# photo-trigger.net
KiCad netlist of a schematic drawn in EAGLE
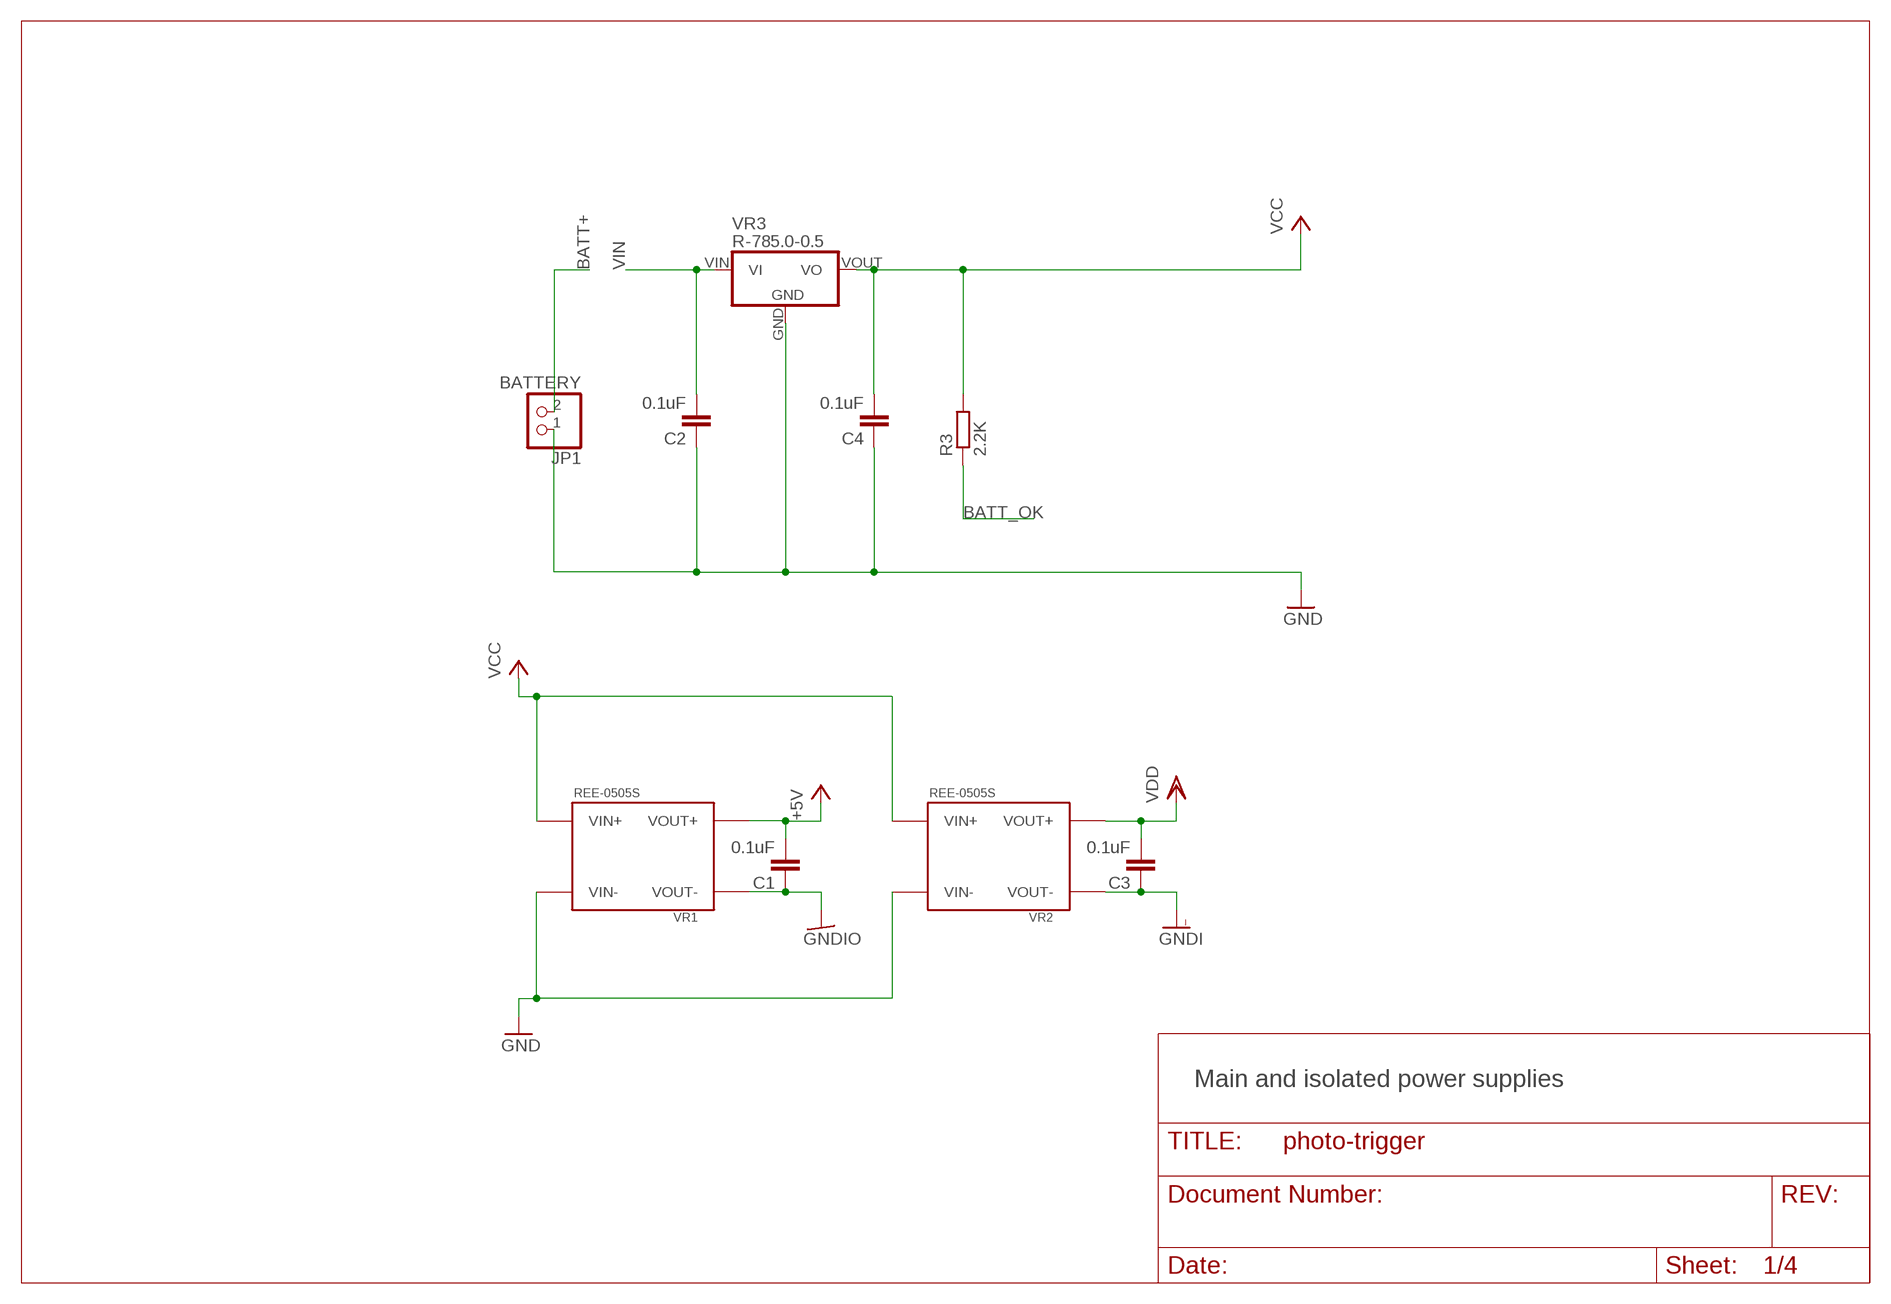
[diagram p0: schematic, sheet 1]
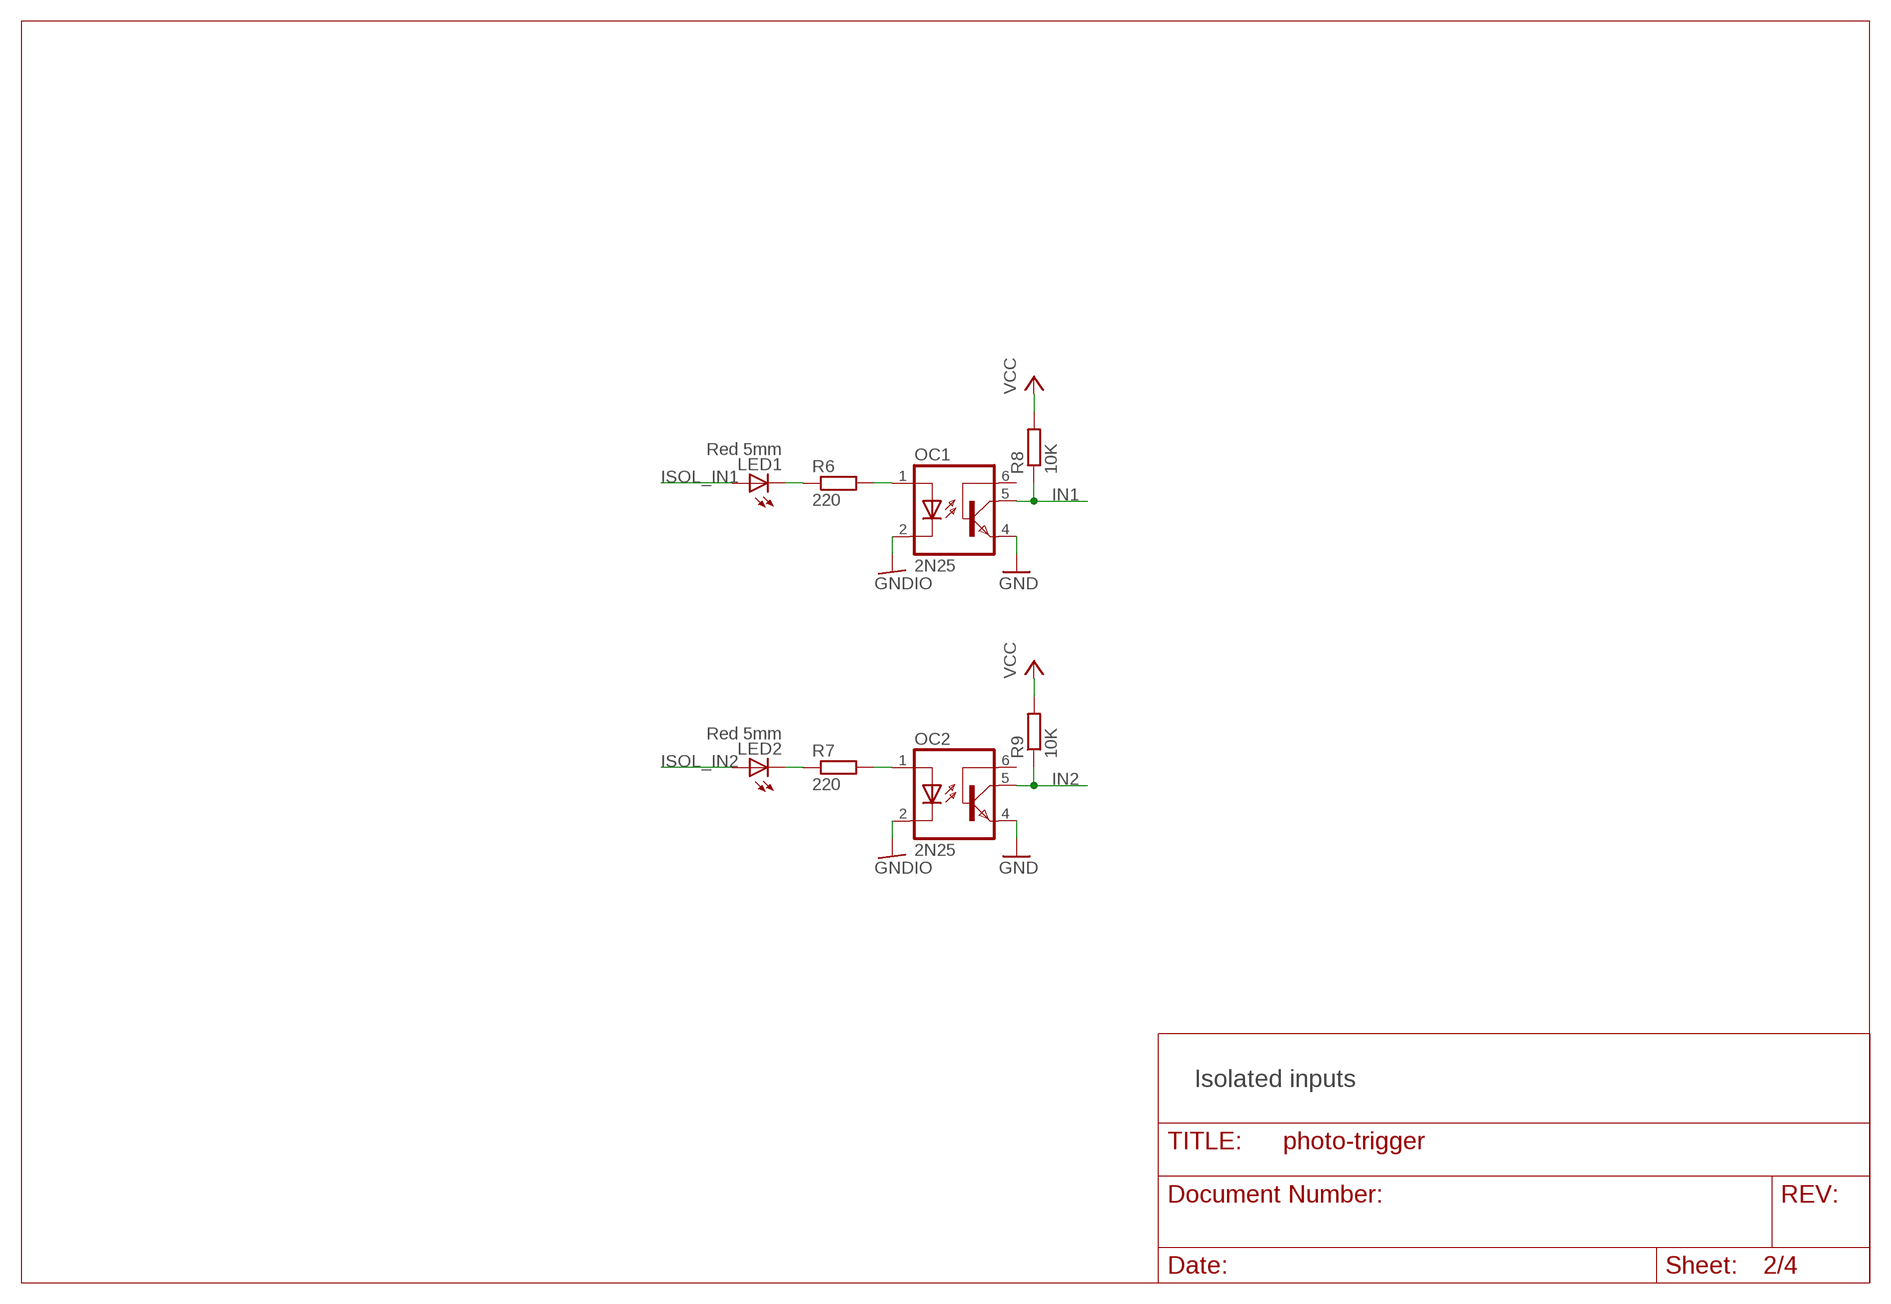
[diagram p1: schematic, sheet 2]
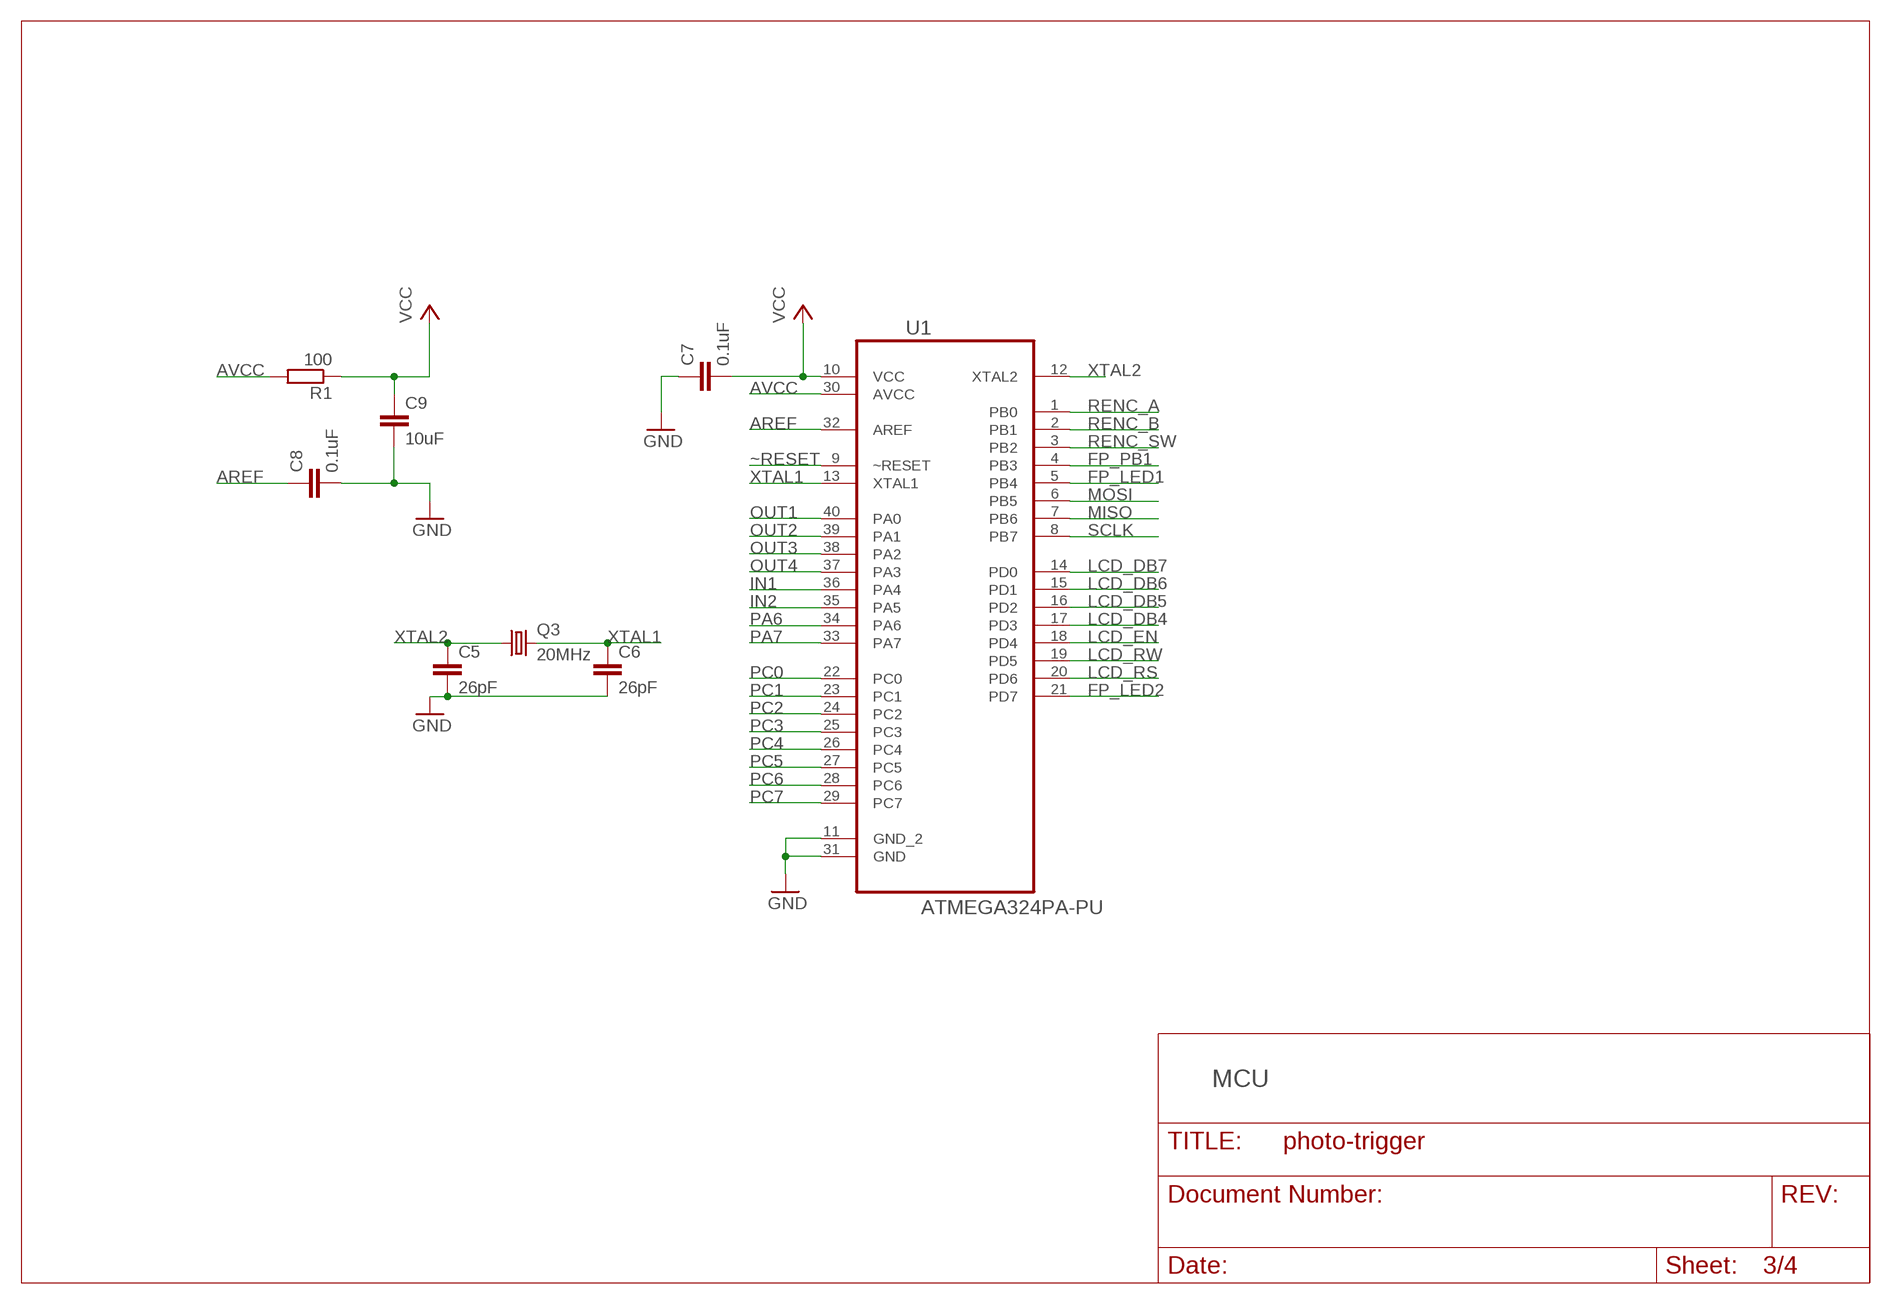
[diagram p2: schematic, sheet 3]
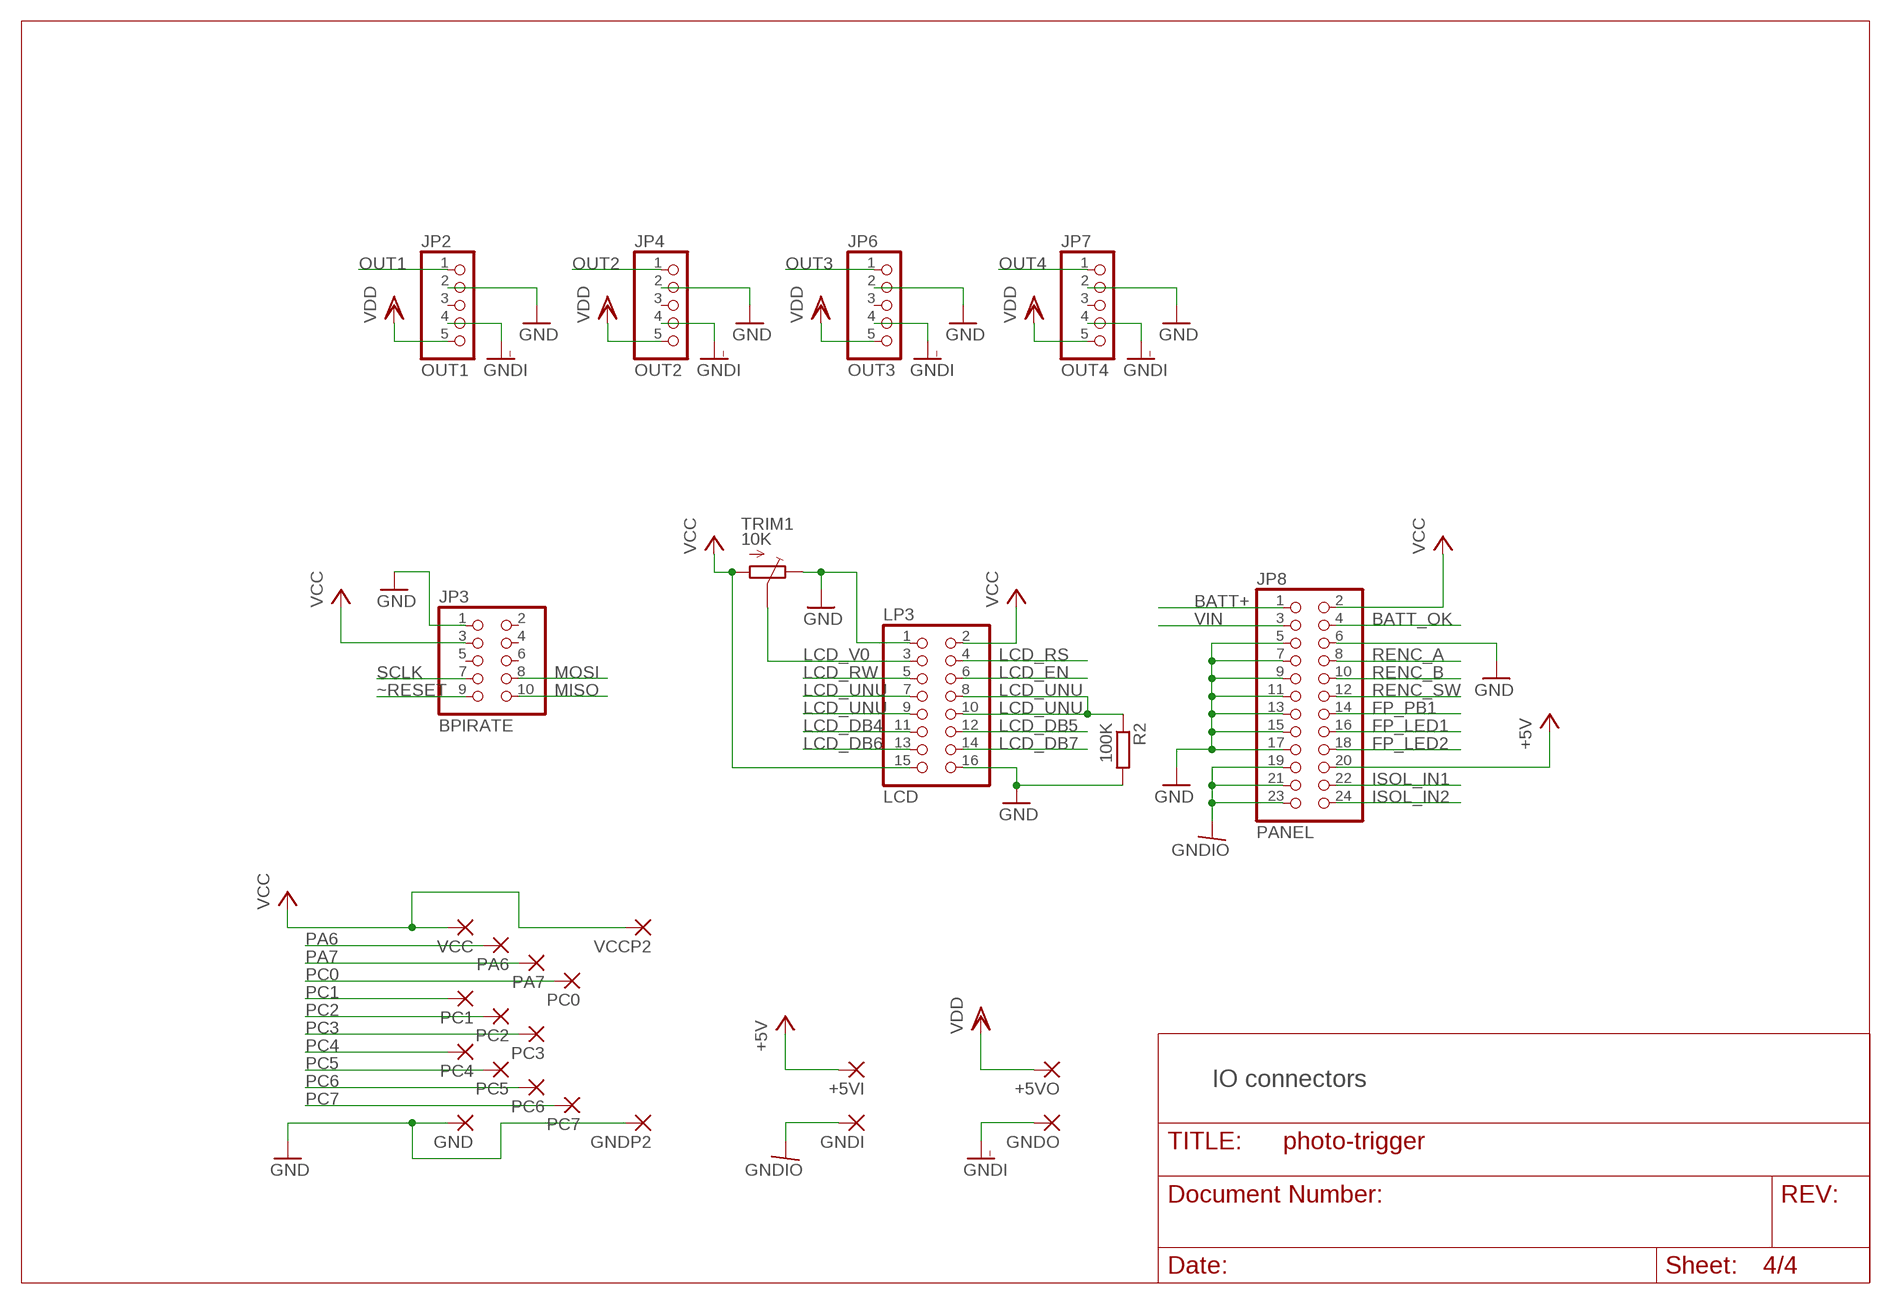
[diagram p3: schematic, sheet 4]

(export (version "E")
  (design (tool "Eeschema 10.0.6"))
  (components
    (comp (ref "+5VI")
      (value "+5VI")
      (footprint "eagle-import:PAD1.9_0.9")
      (libsource (lib "eagle-import") (part "PAD1.9/0.9"))
    )
    (comp (ref "+5VO")
      (value "+5VO")
      (footprint "eagle-import:PAD1.9_0.9")
      (libsource (lib "eagle-import") (part "PAD1.9/0.9"))
    )
    (comp (ref "GND")
      (value "GND")
      (footprint "eagle-import:PAD1.9_0.9")
      (libsource (lib "eagle-import") (part "PAD1.9/0.9"))
    )
    (comp (ref "GNDI")
      (value "GNDI")
      (footprint "eagle-import:PAD1.9_0.9")
      (libsource (lib "eagle-import") (part "PAD1.9/0.9"))
    )
    (comp (ref "GNDO")
      (value "GNDO")
      (footprint "eagle-import:PAD1.9_0.9")
      (libsource (lib "eagle-import") (part "PAD1.9/0.9"))
    )
    (comp (ref "GNDP2")
      (value "GND")
      (footprint "eagle-import:PAD1.9_0.9")
      (libsource (lib "eagle-import") (part "PAD1.9/0.9"))
    )
    (comp (ref "JP2")
      (value "OUT1")
      (footprint "eagle-import:1X05")
      (libsource (lib "eagle-import") (part "PINHD-1X5"))
    )
    (comp (ref "JP3")
      (value "BPIRATE")
      (footprint "eagle-import:2X05")
      (libsource (lib "eagle-import") (part "PINHD-2X5"))
    )
    (comp (ref "JP4")
      (value "OUT2")
      (footprint "eagle-import:1X05")
      (libsource (lib "eagle-import") (part "PINHD-1X5"))
    )
    (comp (ref "JP6")
      (value "OUT3")
      (footprint "eagle-import:1X05")
      (libsource (lib "eagle-import") (part "PINHD-1X5"))
    )
    (comp (ref "JP7")
      (value "OUT4")
      (footprint "eagle-import:1X05")
      (libsource (lib "eagle-import") (part "PINHD-1X5"))
    )
    (comp (ref "JP8")
      (value "PANEL")
      (footprint "eagle-import:2X12")
      (libsource (lib "eagle-import") (part "PINHD-2X12"))
    )
    (comp (ref "LP3")
      (value "LCD")
      (footprint "eagle-import:2X08")
      (libsource (lib "eagle-import") (part "PINHD-2X8"))
    )
    (comp (ref "PA6")
      (value "PA2")
      (footprint "eagle-import:PAD1.9_0.9")
      (libsource (lib "eagle-import") (part "PAD1.9/0.9"))
    )
    (comp (ref "PA7")
      (value "PA3")
      (footprint "eagle-import:PAD1.9_0.9")
      (libsource (lib "eagle-import") (part "PAD1.9/0.9"))
    )
    (comp (ref "PC0")
      (value "PC0")
      (footprint "eagle-import:PAD1.9_0.9")
      (libsource (lib "eagle-import") (part "PAD1.9/0.9"))
    )
    (comp (ref "PC1")
      (value "PC1")
      (footprint "eagle-import:PAD1.9_0.9")
      (libsource (lib "eagle-import") (part "PAD1.9/0.9"))
    )
    (comp (ref "PC2")
      (value "PC2")
      (footprint "eagle-import:PAD1.9_0.9")
      (libsource (lib "eagle-import") (part "PAD1.9/0.9"))
    )
    (comp (ref "PC3")
      (value "PC3")
      (footprint "eagle-import:PAD1.9_0.9")
      (libsource (lib "eagle-import") (part "PAD1.9/0.9"))
    )
    (comp (ref "PC4")
      (value "PC4")
      (footprint "eagle-import:PAD1.9_0.9")
      (libsource (lib "eagle-import") (part "PAD1.9/0.9"))
    )
    (comp (ref "PC5")
      (value "PC5")
      (footprint "eagle-import:PAD1.9_0.9")
      (libsource (lib "eagle-import") (part "PAD1.9/0.9"))
    )
    (comp (ref "PC6")
      (value "PC6")
      (footprint "eagle-import:PAD1.9_0.9")
      (libsource (lib "eagle-import") (part "PAD1.9/0.9"))
    )
    (comp (ref "PC7")
      (value "PC7")
      (footprint "eagle-import:PAD1.9_0.9")
      (libsource (lib "eagle-import") (part "PAD1.9/0.9"))
    )
    (comp (ref "R2")
      (value "100K")
      (footprint "eagle-import:0207_10")
      (libsource (lib "eagle-import") (part "R-EU_0207/10"))
    )
    (comp (ref "TRIM1")
      (value "10K")
      (footprint "eagle-import:VISHAY-TRIM-63M-T607")
      (libsource (lib "eagle-import") (part "VISHAY-63M-T607"))
    )
    (comp (ref "VCC")
      (value "VCC")
      (footprint "eagle-import:PAD1.9_0.9")
      (libsource (lib "eagle-import") (part "PAD1.9/0.9"))
    )
    (comp (ref "VCCP2")
      (value "VCC")
      (footprint "eagle-import:PAD1.9_0.9")
      (libsource (lib "eagle-import") (part "PAD1.9/0.9"))
    )
    (comp (ref "C1")
      (value "0.1uF")
      (footprint "eagle-import:C050-035X075")
      (libsource (lib "eagle-import") (part "C-EU050-035X075"))
    )
    (comp (ref "C2")
      (value "0.1uF")
      (footprint "eagle-import:C050-035X075")
      (libsource (lib "eagle-import") (part "C-EU050-035X075"))
    )
    (comp (ref "C3")
      (value "0.1uF")
      (footprint "eagle-import:C050-035X075")
      (libsource (lib "eagle-import") (part "C-EU050-035X075"))
    )
    (comp (ref "C4")
      (value "0.1uF")
      (footprint "eagle-import:C050-035X075")
      (libsource (lib "eagle-import") (part "C-EU050-035X075"))
    )
    (comp (ref "JP1")
      (value "BATTERY")
      (footprint "eagle-import:1X02")
      (libsource (lib "eagle-import") (part "PINHD-1X2"))
    )
    (comp (ref "R3")
      (value "2.2K")
      (footprint "eagle-import:0207_10")
      (libsource (lib "eagle-import") (part "R-EU_0207/10"))
    )
    (comp (ref "VR1")
      (value "REE-0505S")
      (footprint "eagle-import:RECOM-REE")
      (libsource (lib "eagle-import") (part "RECOM-REE-0505S"))
    )
    (comp (ref "VR2")
      (value "REE-0505S")
      (footprint "eagle-import:RECOM-REE")
      (libsource (lib "eagle-import") (part "RECOM-REE-0505S"))
    )
    (comp (ref "VR3")
      (value "R-785.0-0.5")
      (footprint "eagle-import:RECOM-R78")
      (libsource (lib "eagle-import") (part "RECOM-R-785.0-0.5"))
    )
    (comp (ref "C5")
      (value "26pF")
      (footprint "eagle-import:C025-025X050")
      (libsource (lib "eagle-import") (part "C-EU025-025X050"))
    )
    (comp (ref "C6")
      (value "26pF")
      (footprint "eagle-import:C025-025X050")
      (libsource (lib "eagle-import") (part "C-EU025-025X050"))
    )
    (comp (ref "C7")
      (value "0.1uF")
      (footprint "eagle-import:C050-035X075")
      (libsource (lib "eagle-import") (part "C-EU050-035X075"))
    )
    (comp (ref "C8")
      (value "0.1uF")
      (footprint "eagle-import:C050-035X075")
      (libsource (lib "eagle-import") (part "C-EU050-035X075"))
    )
    (comp (ref "C9")
      (value "10uF")
      (footprint "eagle-import:C050-035X075")
      (libsource (lib "eagle-import") (part "C-EU050-035X075"))
    )
    (comp (ref "Q3")
      (value "20MHz")
      (footprint "eagle-import:HC49_S")
      (libsource (lib "eagle-import") (part "CRYSTALHC49S"))
    )
    (comp (ref "R1")
      (value "100")
      (footprint "eagle-import:0207_10")
      (libsource (lib "eagle-import") (part "R-EU_0207/10"))
    )
    (comp (ref "U1")
      (value "ATMEGA324PA-PU")
      (footprint "eagle-import:DIP254P1524X482-40")
      (libsource (lib "eagle-import") (part "ATMEGA324PA-PU"))
    )
    (comp (ref "LED1")
      (value "Red 5mm")
      (footprint "eagle-import:LED5MM")
      (libsource (lib "eagle-import") (part "LED5MM"))
    )
    (comp (ref "LED2")
      (value "Red 5mm")
      (footprint "eagle-import:LED5MM")
      (libsource (lib "eagle-import") (part "LED5MM"))
    )
    (comp (ref "OC1")
      (value "2N25")
      (footprint "eagle-import:DIL-06")
      (libsource (lib "eagle-import") (part "2N25"))
    )
    (comp (ref "OC2")
      (value "2N25")
      (footprint "eagle-import:DIL-06")
      (libsource (lib "eagle-import") (part "2N25"))
    )
    (comp (ref "R6")
      (value "220")
      (footprint "eagle-import:0207_10")
      (libsource (lib "eagle-import") (part "resistor_R-EU_0207/10"))
    )
    (comp (ref "R7")
      (value "220")
      (footprint "eagle-import:0207_10")
      (libsource (lib "eagle-import") (part "resistor_R-EU_0207/10"))
    )
    (comp (ref "R8")
      (value "10K")
      (footprint "eagle-import:0207_10")
      (libsource (lib "eagle-import") (part "resistor_R-EU_0207/10"))
    )
    (comp (ref "R9")
      (value "10K")
      (footprint "eagle-import:0207_10")
      (libsource (lib "eagle-import") (part "resistor_R-EU_0207/10"))
    )
  )
  (nets
    (net (code "1") (name "+5V") (class "Default")
      (node (ref "+5VI") (pin "P$1") (pinfunction "P_P$1") (pintype "passive"))
      (node (ref "C1") (pin "2") (pinfunction "2_2") (pintype "passive"))
      (node (ref "JP8") (pin "20") (pinfunction "20_20") (pintype "passive"))
      (node (ref "VR1") (pin "VOUT+") (pinfunction "VOUT+_VOUT+") (pintype "bidirectional"))
    )
    (net (code "2") (name "AREF") (class "Default")
      (node (ref "C8") (pin "1") (pinfunction "1_1") (pintype "passive"))
      (node (ref "U1") (pin "32") (pinfunction "AREF_32") (pintype "input"))
    )
    (net (code "3") (name "AVCC") (class "Default")
      (node (ref "R1") (pin "2") (pinfunction "2_2") (pintype "passive"))
      (node (ref "U1") (pin "30") (pinfunction "AVCC_30") (pintype "power_in"))
    )
    (net (code "4") (name "BATT+") (class "Default")
      (node (ref "JP1") (pin "2") (pinfunction "2_2") (pintype "passive"))
      (node (ref "JP8") (pin "1") (pinfunction "1_1") (pintype "passive"))
    )
    (net (code "5") (name "BATT_OK") (class "Default")
      (node (ref "JP8") (pin "4") (pinfunction "4_4") (pintype "passive"))
      (node (ref "R3") (pin "1") (pinfunction "1_1") (pintype "passive"))
    )
    (net (code "6") (name "FP_LED1") (class "Default")
      (node (ref "JP8") (pin "16") (pinfunction "16_16") (pintype "passive"))
      (node (ref "U1") (pin "5") (pinfunction "PB4_5") (pintype "bidirectional"))
    )
    (net (code "7") (name "FP_LED2") (class "Default")
      (node (ref "JP8") (pin "18") (pinfunction "18_18") (pintype "passive"))
      (node (ref "U1") (pin "21") (pinfunction "PD7_21") (pintype "bidirectional"))
    )
    (net (code "8") (name "FP_PB1") (class "Default")
      (node (ref "JP8") (pin "14") (pinfunction "14_14") (pintype "passive"))
      (node (ref "U1") (pin "4") (pinfunction "PB3_4") (pintype "bidirectional"))
    )
    (net (code "9") (name "GND") (class "Default")
      (node (ref "C2") (pin "1") (pinfunction "1_1") (pintype "passive"))
      (node (ref "C4") (pin "1") (pinfunction "1_1") (pintype "passive"))
      (node (ref "C5") (pin "2") (pinfunction "2_2") (pintype "passive"))
      (node (ref "C6") (pin "2") (pinfunction "2_2") (pintype "passive"))
      (node (ref "C7") (pin "1") (pinfunction "1_1") (pintype "passive"))
      (node (ref "C8") (pin "2") (pinfunction "2_2") (pintype "passive"))
      (node (ref "C9") (pin "2") (pinfunction "2_2") (pintype "passive"))
      (node (ref "GND") (pin "P$1") (pinfunction "P_P$1") (pintype "passive"))
      (node (ref "GNDP2") (pin "P$1") (pinfunction "P_P$1") (pintype "passive"))
      (node (ref "JP1") (pin "1") (pinfunction "1_1") (pintype "passive"))
      (node (ref "JP2") (pin "2") (pinfunction "2_2") (pintype "passive"))
      (node (ref "JP3") (pin "1") (pinfunction "1_1") (pintype "passive"))
      (node (ref "JP4") (pin "2") (pinfunction "2_2") (pintype "passive"))
      (node (ref "JP6") (pin "2") (pinfunction "2_2") (pintype "passive"))
      (node (ref "JP7") (pin "2") (pinfunction "2_2") (pintype "passive"))
      (node (ref "JP8") (pin "11") (pinfunction "11_11") (pintype "passive"))
      (node (ref "JP8") (pin "13") (pinfunction "13_13") (pintype "passive"))
      (node (ref "JP8") (pin "15") (pinfunction "15_15") (pintype "passive"))
      (node (ref "JP8") (pin "17") (pinfunction "17_17") (pintype "passive"))
      (node (ref "JP8") (pin "5") (pinfunction "5_5") (pintype "passive"))
      (node (ref "JP8") (pin "6") (pinfunction "6_6") (pintype "passive"))
      (node (ref "JP8") (pin "7") (pinfunction "7_7") (pintype "passive"))
      (node (ref "JP8") (pin "9") (pinfunction "9_9") (pintype "passive"))
      (node (ref "LP3") (pin "1") (pinfunction "1_1") (pintype "passive"))
      (node (ref "LP3") (pin "16") (pinfunction "16_16") (pintype "passive"))
      (node (ref "OC1") (pin "4") (pinfunction "EMI_4") (pintype "passive"))
      (node (ref "OC2") (pin "4") (pinfunction "EMI_4") (pintype "passive"))
      (node (ref "R2") (pin "2") (pinfunction "2_2") (pintype "passive"))
      (node (ref "TRIM1") (pin "P$3") (pinfunction "E_P$3") (pintype "passive"))
      (node (ref "U1") (pin "11") (pinfunction "GND_2_11") (pintype "passive"))
      (node (ref "U1") (pin "31") (pinfunction "GND_31") (pintype "passive"))
      (node (ref "VR1") (pin "VIN-") (pinfunction "VIN-_VIN-") (pintype "bidirectional"))
      (node (ref "VR2") (pin "VIN-") (pinfunction "VIN-_VIN-") (pintype "bidirectional"))
      (node (ref "VR3") (pin "GND") (pinfunction "GND_GND") (pintype "passive"))
    )
    (net (code "10") (name "GNDI") (class "Default")
      (node (ref "C3") (pin "1") (pinfunction "1_1") (pintype "passive"))
      (node (ref "GNDO") (pin "P$1") (pinfunction "P_P$1") (pintype "passive"))
      (node (ref "JP2") (pin "4") (pinfunction "4_4") (pintype "passive"))
      (node (ref "JP4") (pin "4") (pinfunction "4_4") (pintype "passive"))
      (node (ref "JP6") (pin "4") (pinfunction "4_4") (pintype "passive"))
      (node (ref "JP7") (pin "4") (pinfunction "4_4") (pintype "passive"))
      (node (ref "VR2") (pin "VOUT-") (pinfunction "VOUT-_VOUT-") (pintype "bidirectional"))
    )
    (net (code "11") (name "GNDIO") (class "Default")
      (node (ref "C1") (pin "1") (pinfunction "1_1") (pintype "passive"))
      (node (ref "GNDI") (pin "P$1") (pinfunction "P_P$1") (pintype "passive"))
      (node (ref "JP8") (pin "19") (pinfunction "19_19") (pintype "passive"))
      (node (ref "JP8") (pin "21") (pinfunction "21_21") (pintype "passive"))
      (node (ref "JP8") (pin "23") (pinfunction "23_23") (pintype "passive"))
      (node (ref "OC1") (pin "2") (pinfunction "C_2") (pintype "passive"))
      (node (ref "OC2") (pin "2") (pinfunction "C_2") (pintype "passive"))
      (node (ref "VR1") (pin "VOUT-") (pinfunction "VOUT-_VOUT-") (pintype "bidirectional"))
    )
    (net (code "12") (name "IN1") (class "Default")
      (node (ref "OC1") (pin "5") (pinfunction "COL_5") (pintype "passive"))
      (node (ref "R8") (pin "1") (pinfunction "1_1") (pintype "passive"))
      (node (ref "U1") (pin "36") (pinfunction "PA4_36") (pintype "bidirectional"))
    )
    (net (code "13") (name "IN2") (class "Default")
      (node (ref "OC2") (pin "5") (pinfunction "COL_5") (pintype "passive"))
      (node (ref "R9") (pin "1") (pinfunction "1_1") (pintype "passive"))
      (node (ref "U1") (pin "35") (pinfunction "PA5_35") (pintype "bidirectional"))
    )
    (net (code "14") (name "ISOL_IN1") (class "Default")
      (node (ref "JP8") (pin "22") (pinfunction "22_22") (pintype "passive"))
      (node (ref "LED1") (pin "A") (pinfunction "A_A") (pintype "passive"))
    )
    (net (code "15") (name "ISOL_IN2") (class "Default")
      (node (ref "JP8") (pin "24") (pinfunction "24_24") (pintype "passive"))
      (node (ref "LED2") (pin "A") (pinfunction "A_A") (pintype "passive"))
    )
    (net (code "16") (name "LCD_DB4") (class "Default")
      (node (ref "LP3") (pin "11") (pinfunction "11_11") (pintype "passive"))
      (node (ref "U1") (pin "17") (pinfunction "PD3_17") (pintype "bidirectional"))
    )
    (net (code "17") (name "LCD_DB5") (class "Default")
      (node (ref "LP3") (pin "12") (pinfunction "12_12") (pintype "passive"))
      (node (ref "U1") (pin "16") (pinfunction "PD2_16") (pintype "bidirectional"))
    )
    (net (code "18") (name "LCD_DB6") (class "Default")
      (node (ref "LP3") (pin "13") (pinfunction "13_13") (pintype "passive"))
      (node (ref "U1") (pin "15") (pinfunction "PD1_15") (pintype "bidirectional"))
    )
    (net (code "19") (name "LCD_DB7") (class "Default")
      (node (ref "LP3") (pin "14") (pinfunction "14_14") (pintype "passive"))
      (node (ref "U1") (pin "14") (pinfunction "PD0_14") (pintype "bidirectional"))
    )
    (net (code "20") (name "LCD_EN") (class "Default")
      (node (ref "LP3") (pin "6") (pinfunction "6_6") (pintype "passive"))
      (node (ref "U1") (pin "18") (pinfunction "PD4_18") (pintype "bidirectional"))
    )
    (net (code "21") (name "LCD_RS") (class "Default")
      (node (ref "LP3") (pin "4") (pinfunction "4_4") (pintype "passive"))
      (node (ref "U1") (pin "20") (pinfunction "PD6_20") (pintype "bidirectional"))
    )
    (net (code "22") (name "LCD_RW") (class "Default")
      (node (ref "LP3") (pin "5") (pinfunction "5_5") (pintype "passive"))
      (node (ref "U1") (pin "19") (pinfunction "PD5_19") (pintype "bidirectional"))
    )
    (net (code "23") (name "LCD_UNU") (class "Default")
      (node (ref "LP3") (pin "10") (pinfunction "10_10") (pintype "passive"))
      (node (ref "LP3") (pin "7") (pinfunction "7_7") (pintype "passive"))
      (node (ref "LP3") (pin "8") (pinfunction "8_8") (pintype "passive"))
      (node (ref "LP3") (pin "9") (pinfunction "9_9") (pintype "passive"))
      (node (ref "R2") (pin "1") (pinfunction "1_1") (pintype "passive"))
    )
    (net (code "24") (name "LCD_V0") (class "Default")
      (node (ref "LP3") (pin "3") (pinfunction "3_3") (pintype "passive"))
      (node (ref "TRIM1") (pin "P$2") (pinfunction "S_P$2") (pintype "passive"))
    )
    (net (code "25") (name "MISO") (class "Default")
      (node (ref "JP3") (pin "10") (pinfunction "10_10") (pintype "passive"))
      (node (ref "U1") (pin "7") (pinfunction "PB6_7") (pintype "bidirectional"))
    )
    (net (code "26") (name "MOSI") (class "Default")
      (node (ref "JP3") (pin "8") (pinfunction "8_8") (pintype "passive"))
      (node (ref "U1") (pin "6") (pinfunction "PB5_6") (pintype "bidirectional"))
    )
    (net (code "27") (name "Net-(LED1-C)") (class "Default")
      (node (ref "LED1") (pin "K") (pinfunction "C_K") (pintype "passive"))
      (node (ref "R6") (pin "1") (pinfunction "1_1") (pintype "passive"))
    )
    (net (code "28") (name "Net-(LED2-C)") (class "Default")
      (node (ref "LED2") (pin "K") (pinfunction "C_K") (pintype "passive"))
      (node (ref "R7") (pin "1") (pinfunction "1_1") (pintype "passive"))
    )
    (net (code "29") (name "Net-(OC1-A)") (class "Default")
      (node (ref "OC1") (pin "1") (pinfunction "A_1") (pintype "passive"))
      (node (ref "R6") (pin "2") (pinfunction "2_2") (pintype "passive"))
    )
    (net (code "30") (name "Net-(OC2-A)") (class "Default")
      (node (ref "OC2") (pin "1") (pinfunction "A_1") (pintype "passive"))
      (node (ref "R7") (pin "2") (pinfunction "2_2") (pintype "passive"))
    )
    (net (code "31") (name "OUT1") (class "Default")
      (node (ref "JP2") (pin "1") (pinfunction "1_1") (pintype "passive"))
      (node (ref "U1") (pin "40") (pinfunction "PA0_40") (pintype "bidirectional"))
    )
    (net (code "32") (name "OUT2") (class "Default")
      (node (ref "JP4") (pin "1") (pinfunction "1_1") (pintype "passive"))
      (node (ref "U1") (pin "39") (pinfunction "PA1_39") (pintype "bidirectional"))
    )
    (net (code "33") (name "OUT3") (class "Default")
      (node (ref "JP6") (pin "1") (pinfunction "1_1") (pintype "passive"))
      (node (ref "U1") (pin "38") (pinfunction "PA2_38") (pintype "bidirectional"))
    )
    (net (code "34") (name "OUT4") (class "Default")
      (node (ref "JP7") (pin "1") (pinfunction "1_1") (pintype "passive"))
      (node (ref "U1") (pin "37") (pinfunction "PA3_37") (pintype "bidirectional"))
    )
    (net (code "35") (name "PA6") (class "Default")
      (node (ref "PA6") (pin "P$1") (pinfunction "P_P$1") (pintype "passive"))
      (node (ref "U1") (pin "34") (pinfunction "PA6_34") (pintype "bidirectional"))
    )
    (net (code "36") (name "PA7") (class "Default")
      (node (ref "PA7") (pin "P$1") (pinfunction "P_P$1") (pintype "passive"))
      (node (ref "U1") (pin "33") (pinfunction "PA7_33") (pintype "bidirectional"))
    )
    (net (code "37") (name "PC0") (class "Default")
      (node (ref "PC0") (pin "P$1") (pinfunction "P_P$1") (pintype "passive"))
      (node (ref "U1") (pin "22") (pinfunction "PC0_22") (pintype "bidirectional"))
    )
    (net (code "38") (name "PC1") (class "Default")
      (node (ref "PC1") (pin "P$1") (pinfunction "P_P$1") (pintype "passive"))
      (node (ref "U1") (pin "23") (pinfunction "PC1_23") (pintype "bidirectional"))
    )
    (net (code "39") (name "PC2") (class "Default")
      (node (ref "PC2") (pin "P$1") (pinfunction "P_P$1") (pintype "passive"))
      (node (ref "U1") (pin "24") (pinfunction "PC2_24") (pintype "bidirectional"))
    )
    (net (code "40") (name "PC3") (class "Default")
      (node (ref "PC3") (pin "P$1") (pinfunction "P_P$1") (pintype "passive"))
      (node (ref "U1") (pin "25") (pinfunction "PC3_25") (pintype "bidirectional"))
    )
    (net (code "41") (name "PC4") (class "Default")
      (node (ref "PC4") (pin "P$1") (pinfunction "P_P$1") (pintype "passive"))
      (node (ref "U1") (pin "26") (pinfunction "PC4_26") (pintype "bidirectional"))
    )
    (net (code "42") (name "PC5") (class "Default")
      (node (ref "PC5") (pin "P$1") (pinfunction "P_P$1") (pintype "passive"))
      (node (ref "U1") (pin "27") (pinfunction "PC5_27") (pintype "bidirectional"))
    )
    (net (code "43") (name "PC6") (class "Default")
      (node (ref "PC6") (pin "P$1") (pinfunction "P_P$1") (pintype "passive"))
      (node (ref "U1") (pin "28") (pinfunction "PC6_28") (pintype "bidirectional"))
    )
    (net (code "44") (name "PC7") (class "Default")
      (node (ref "PC7") (pin "P$1") (pinfunction "P_P$1") (pintype "passive"))
      (node (ref "U1") (pin "29") (pinfunction "PC7_29") (pintype "bidirectional"))
    )
    (net (code "45") (name "RENC_A") (class "Default")
      (node (ref "JP8") (pin "8") (pinfunction "8_8") (pintype "passive"))
      (node (ref "U1") (pin "1") (pinfunction "PB0_1") (pintype "bidirectional"))
    )
    (net (code "46") (name "RENC_B") (class "Default")
      (node (ref "JP8") (pin "10") (pinfunction "10_10") (pintype "passive"))
      (node (ref "U1") (pin "2") (pinfunction "PB1_2") (pintype "bidirectional"))
    )
    (net (code "47") (name "RENC_SW") (class "Default")
      (node (ref "JP8") (pin "12") (pinfunction "12_12") (pintype "passive"))
      (node (ref "U1") (pin "3") (pinfunction "PB2_3") (pintype "bidirectional"))
    )
    (net (code "48") (name "SCLK") (class "Default")
      (node (ref "JP3") (pin "7") (pinfunction "7_7") (pintype "passive"))
      (node (ref "U1") (pin "8") (pinfunction "PB7_8") (pintype "bidirectional"))
    )
    (net (code "49") (name "VCC") (class "Default")
      (node (ref "C4") (pin "2") (pinfunction "2_2") (pintype "passive"))
      (node (ref "C7") (pin "2") (pinfunction "2_2") (pintype "passive"))
      (node (ref "C9") (pin "1") (pinfunction "1_1") (pintype "passive"))
      (node (ref "JP3") (pin "3") (pinfunction "3_3") (pintype "passive"))
      (node (ref "JP8") (pin "2") (pinfunction "2_2") (pintype "passive"))
      (node (ref "LP3") (pin "15") (pinfunction "15_15") (pintype "passive"))
      (node (ref "LP3") (pin "2") (pinfunction "2_2") (pintype "passive"))
      (node (ref "R1") (pin "1") (pinfunction "1_1") (pintype "passive"))
      (node (ref "R3") (pin "2") (pinfunction "2_2") (pintype "passive"))
      (node (ref "R8") (pin "2") (pinfunction "2_2") (pintype "passive"))
      (node (ref "R9") (pin "2") (pinfunction "2_2") (pintype "passive"))
      (node (ref "TRIM1") (pin "P$1") (pinfunction "A_P$1") (pintype "passive"))
      (node (ref "U1") (pin "10") (pinfunction "VCC_10") (pintype "power_in"))
      (node (ref "VCC") (pin "P$1") (pinfunction "P_P$1") (pintype "passive"))
      (node (ref "VCCP2") (pin "P$1") (pinfunction "P_P$1") (pintype "passive"))
      (node (ref "VR1") (pin "VIN+") (pinfunction "VIN+_VIN+") (pintype "bidirectional"))
      (node (ref "VR2") (pin "VIN+") (pinfunction "VIN+_VIN+") (pintype "bidirectional"))
      (node (ref "VR3") (pin "VOUT") (pinfunction "VO_VOUT") (pintype "passive"))
    )
    (net (code "50") (name "VDD") (class "Default")
      (node (ref "+5VO") (pin "P$1") (pinfunction "P_P$1") (pintype "passive"))
      (node (ref "C3") (pin "2") (pinfunction "2_2") (pintype "passive"))
      (node (ref "JP2") (pin "5") (pinfunction "5_5") (pintype "passive"))
      (node (ref "JP4") (pin "5") (pinfunction "5_5") (pintype "passive"))
      (node (ref "JP6") (pin "5") (pinfunction "5_5") (pintype "passive"))
      (node (ref "JP7") (pin "5") (pinfunction "5_5") (pintype "passive"))
      (node (ref "VR2") (pin "VOUT+") (pinfunction "VOUT+_VOUT+") (pintype "bidirectional"))
    )
    (net (code "51") (name "VIN") (class "Default")
      (node (ref "C2") (pin "2") (pinfunction "2_2") (pintype "passive"))
      (node (ref "JP8") (pin "3") (pinfunction "3_3") (pintype "passive"))
      (node (ref "VR3") (pin "VIN") (pinfunction "VI_VIN") (pintype "input"))
    )
    (net (code "52") (name "XTAL1") (class "Default")
      (node (ref "C6") (pin "1") (pinfunction "1_1") (pintype "passive"))
      (node (ref "Q3") (pin "2") (pinfunction "2_2") (pintype "passive"))
      (node (ref "U1") (pin "13") (pinfunction "XTAL1_13") (pintype "input"))
    )
    (net (code "53") (name "XTAL2") (class "Default")
      (node (ref "C5") (pin "1") (pinfunction "1_1") (pintype "passive"))
      (node (ref "Q3") (pin "1") (pinfunction "1_1") (pintype "passive"))
      (node (ref "U1") (pin "12") (pinfunction "XTAL2_12") (pintype "output"))
    )
    (net (code "54") (name "unconnected-(JP2-Pad3)") (class "Default")
      (node (ref "JP2") (pin "3") (pinfunction "3_3") (pintype "passive"))
    )
    (net (code "55") (name "unconnected-(JP3-Pad2)") (class "Default")
      (node (ref "JP3") (pin "2") (pinfunction "2_2") (pintype "passive"))
    )
    (net (code "56") (name "unconnected-(JP3-Pad4)") (class "Default")
      (node (ref "JP3") (pin "4") (pinfunction "4_4") (pintype "passive"))
    )
    (net (code "57") (name "unconnected-(JP3-Pad5)") (class "Default")
      (node (ref "JP3") (pin "5") (pinfunction "5_5") (pintype "passive"))
    )
    (net (code "58") (name "unconnected-(JP3-Pad6)") (class "Default")
      (node (ref "JP3") (pin "6") (pinfunction "6_6") (pintype "passive"))
    )
    (net (code "59") (name "unconnected-(JP4-Pad3)") (class "Default")
      (node (ref "JP4") (pin "3") (pinfunction "3_3") (pintype "passive"))
    )
    (net (code "60") (name "unconnected-(JP6-Pad3)") (class "Default")
      (node (ref "JP6") (pin "3") (pinfunction "3_3") (pintype "passive"))
    )
    (net (code "61") (name "unconnected-(JP7-Pad3)") (class "Default")
      (node (ref "JP7") (pin "3") (pinfunction "3_3") (pintype "passive"))
    )
    (net (code "62") (name "unconnected-(OC1-BAS-Pad6)") (class "Default")
      (node (ref "OC1") (pin "6") (pinfunction "BAS_6") (pintype "passive"))
    )
    (net (code "63") (name "unconnected-(OC2-BAS-Pad6)") (class "Default")
      (node (ref "OC2") (pin "6") (pinfunction "BAS_6") (pintype "passive"))
    )
    (net (code "64") (name "~{RESET}") (class "Default")
      (node (ref "JP3") (pin "9") (pinfunction "9_9") (pintype "passive"))
      (node (ref "U1") (pin "9") (pinfunction "~{RESET}_9") (pintype "input"))
    )
  )
)
